# Brians_test_board_10.net
KiCad netlist of a schematic drawn in EAGLE
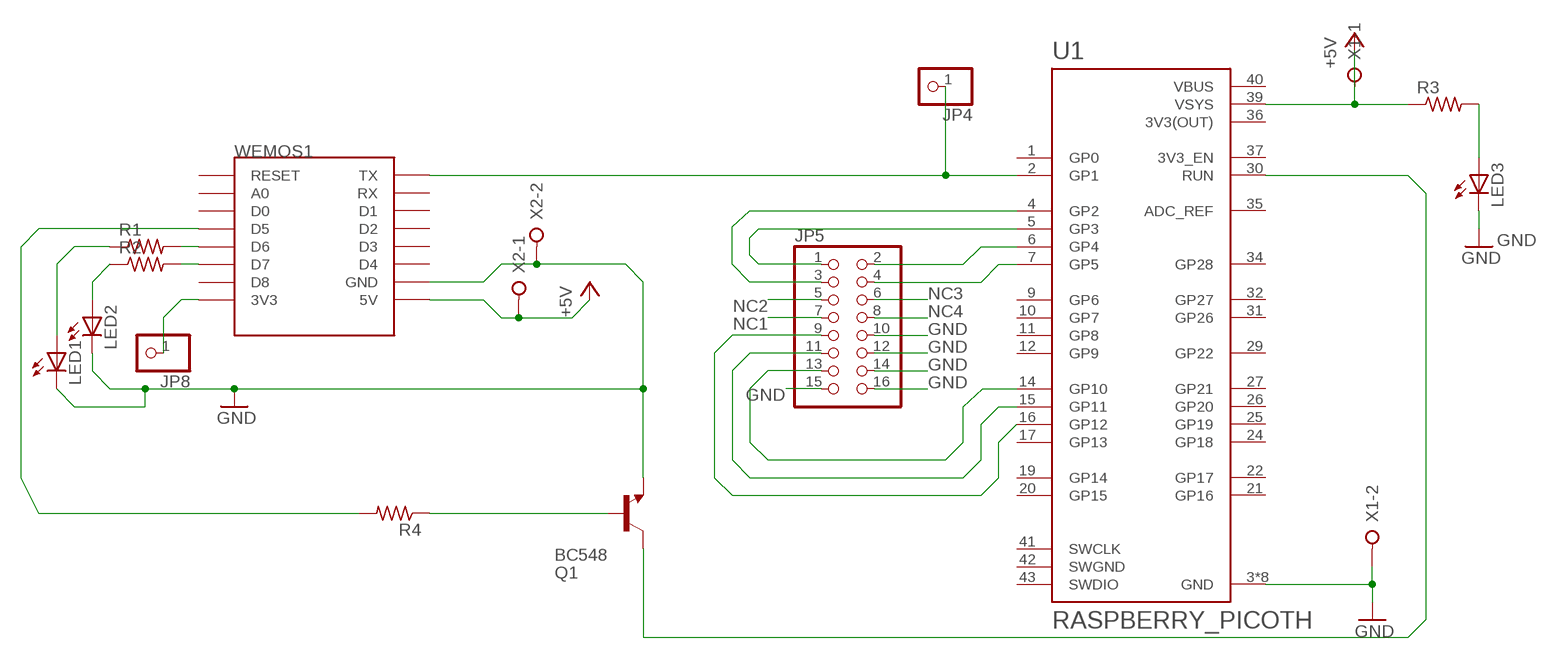
[diagram p0: schematic, sheet 1]

(export (version "E")
  (design (tool "Eeschema 10.0.6"))
  (components
    (comp (ref "JP4")
      (value "PINHD-1X1")
      (footprint "eagle-import:1X01")
      (libsource (lib "eagle-import") (part "PINHD-1X1"))
    )
    (comp (ref "JP5")
      (value "PINHD-2X8")
      (footprint "eagle-import:2X08")
      (libsource (lib "eagle-import") (part "PINHD-2X8"))
    )
    (comp (ref "JP8")
      (value "PINHD-1X1")
      (footprint "eagle-import:1X01")
      (libsource (lib "eagle-import") (part "PINHD-1X1"))
    )
    (comp (ref "LED1")
      (value "LED3MM")
      (footprint "eagle-import:LED3MM")
      (libsource (lib "eagle-import") (part "LED3MM"))
    )
    (comp (ref "LED2")
      (value "LED3MM")
      (footprint "eagle-import:LED3MM")
      (libsource (lib "eagle-import") (part "LED3MM"))
    )
    (comp (ref "LED3")
      (value "LED3MM")
      (footprint "eagle-import:LED3MM")
      (libsource (lib "eagle-import") (part "LED3MM"))
    )
    (comp (ref "Q1")
      (value "BC548")
      (footprint "eagle-import:TO92-EBC")
      (libsource (lib "eagle-import") (part "BC548"))
    )
    (comp (ref "R1")
      (value "R-US_0204/2V")
      (footprint "eagle-import:0204V")
      (libsource (lib "eagle-import") (part "R-US_0204/2V"))
    )
    (comp (ref "R2")
      (value "R-US_0204/2V")
      (footprint "eagle-import:0204V")
      (libsource (lib "eagle-import") (part "R-US_0204/2V"))
    )
    (comp (ref "R3")
      (value "R-US_0204/5")
      (footprint "eagle-import:0204_5")
      (libsource (lib "eagle-import") (part "R-US_0204/5"))
    )
    (comp (ref "R4")
      (value "R-US_0204/2V")
      (footprint "eagle-import:0204V")
      (libsource (lib "eagle-import") (part "R-US_0204/2V"))
    )
    (comp (ref "U1")
      (value "RASPBERRY_PICOTH")
      (footprint "eagle-import:PICO-PKG-TH")
      (libsource (lib "eagle-import") (part "RASPBERRY_PICOTH"))
    )
    (comp (ref "WEMOS1")
      (value "WEMOS-D1-MINI")
      (footprint "eagle-import:WEMOS-D1-MINI")
      (libsource (lib "eagle-import") (part "WEMOS-D1-MINI"))
    )
    (comp (ref "X1")
      (value "W237-02P")
      (footprint "eagle-import:W237-132")
      (libsource (lib "eagle-import") (part "W237-02P"))
    )
    (comp (ref "X2")
      (value "W237-02P")
      (footprint "eagle-import:W237-132")
      (libsource (lib "eagle-import") (part "W237-02P"))
    )
  )
  (nets
    (net (code "1") (name "+5V") (class "Default")
      (node (ref "R3") (pin "1") (pinfunction "1_1") (pintype "passive"))
      (node (ref "U1") (pin "39") (pinfunction "VSYS_39") (pintype "power_in"))
      (node (ref "WEMOS1") (pin "5V") (pinfunction "5V_5V") (pintype "bidirectional"))
      (node (ref "X1") (pin "1") (pinfunction "KL_1") (pintype "passive"))
      (node (ref "X2") (pin "1") (pinfunction "KL_1") (pintype "passive"))
    )
    (net (code "2") (name "/3V3(OUT)") (class "Default")
      (node (ref "U1") (pin "36") (pinfunction "3V3(OUT)_36") (pintype "power_in"))
    )
    (net (code "3") (name "/NC1") (class "Default")
      (node (ref "JP5") (pin "7") (pinfunction "7_7") (pintype "passive"))
    )
    (net (code "4") (name "/NC2") (class "Default")
      (node (ref "JP5") (pin "5") (pinfunction "5_5") (pintype "passive"))
    )
    (net (code "5") (name "/NC3") (class "Default")
      (node (ref "JP5") (pin "6") (pinfunction "6_6") (pintype "passive"))
    )
    (net (code "6") (name "/NC4") (class "Default")
      (node (ref "JP5") (pin "8") (pinfunction "8_8") (pintype "passive"))
    )
    (net (code "7") (name "/SWGND") (class "Default")
      (node (ref "U1") (pin "42") (pinfunction "SWGND_42") (pintype "power_in"))
    )
    (net (code "8") (name "/VBUS") (class "Default")
      (node (ref "U1") (pin "40") (pinfunction "VBUS_40") (pintype "power_in"))
    )
    (net (code "9") (name "GND") (class "Default")
      (node (ref "JP5") (pin "10") (pinfunction "10_10") (pintype "passive"))
      (node (ref "JP5") (pin "12") (pinfunction "12_12") (pintype "passive"))
      (node (ref "JP5") (pin "14") (pinfunction "14_14") (pintype "passive"))
      (node (ref "JP5") (pin "15") (pinfunction "15_15") (pintype "passive"))
      (node (ref "JP5") (pin "16") (pinfunction "16_16") (pintype "passive"))
      (node (ref "LED1") (pin "K") (pinfunction "C_K") (pintype "passive"))
      (node (ref "LED2") (pin "K") (pinfunction "C_K") (pintype "passive"))
      (node (ref "LED3") (pin "K") (pinfunction "C_K") (pintype "passive"))
      (node (ref "Q1") (pin "E") (pinfunction "E_E") (pintype "passive"))
      (node (ref "U1") (pin "13") (pinfunction "GND_13") (pintype "power_in"))
      (node (ref "U1") (pin "18") (pinfunction "GND_18") (pintype "power_in"))
      (node (ref "U1") (pin "23") (pinfunction "GND_23") (pintype "power_in"))
      (node (ref "U1") (pin "28") (pinfunction "GND_28") (pintype "power_in"))
      (node (ref "U1") (pin "3") (pinfunction "GND_3") (pintype "power_in"))
      (node (ref "U1") (pin "33") (pinfunction "GND_33") (pintype "power_in"))
      (node (ref "U1") (pin "38") (pinfunction "GND_38") (pintype "power_in"))
      (node (ref "U1") (pin "8") (pinfunction "GND_8") (pintype "power_in"))
      (node (ref "WEMOS1") (pin "GND") (pinfunction "GND_GND") (pintype "bidirectional"))
      (node (ref "X1") (pin "2") (pinfunction "KL_2") (pintype "passive"))
      (node (ref "X2") (pin "2") (pinfunction "KL_2") (pintype "passive"))
    )
    (net (code "10") (name "Net-(JP8-Pad1)") (class "Default")
      (node (ref "JP8") (pin "1") (pinfunction "1_1") (pintype "passive"))
      (node (ref "WEMOS1") (pin "3V3") (pinfunction "3V3_3V3") (pintype "bidirectional"))
    )
    (net (code "11") (name "Net-(LED1-PadA)") (class "Default")
      (node (ref "LED1") (pin "A") (pinfunction "A_A") (pintype "passive"))
      (node (ref "R1") (pin "1") (pinfunction "1_1") (pintype "passive"))
    )
    (net (code "12") (name "Net-(LED2-PadA)") (class "Default")
      (node (ref "LED2") (pin "A") (pinfunction "A_A") (pintype "passive"))
      (node (ref "R2") (pin "1") (pinfunction "1_1") (pintype "passive"))
    )
    (net (code "13") (name "Net-(LED3-PadA)") (class "Default")
      (node (ref "LED3") (pin "A") (pinfunction "A_A") (pintype "passive"))
      (node (ref "R3") (pin "2") (pinfunction "2_2") (pintype "passive"))
    )
    (net (code "14") (name "Net-(Q1-PadB)") (class "Default")
      (node (ref "Q1") (pin "B") (pinfunction "B_B") (pintype "passive"))
      (node (ref "R4") (pin "1") (pinfunction "1_1") (pintype "passive"))
    )
    (net (code "15") (name "Net-(R1-Pad2)") (class "Default")
      (node (ref "R1") (pin "2") (pinfunction "2_2") (pintype "passive"))
      (node (ref "WEMOS1") (pin "D6") (pinfunction "D6_D6") (pintype "bidirectional"))
    )
    (net (code "16") (name "Net-(R2-Pad2)") (class "Default")
      (node (ref "R2") (pin "2") (pinfunction "2_2") (pintype "passive"))
      (node (ref "WEMOS1") (pin "D7") (pinfunction "D7_D7") (pintype "bidirectional"))
    )
    (net (code "17") (name "Net-(R4-Pad2)") (class "Default")
      (node (ref "R4") (pin "2") (pinfunction "2_2") (pintype "passive"))
      (node (ref "WEMOS1") (pin "D5") (pinfunction "D5_D5") (pintype "bidirectional"))
    )
    (net (code "18") (name "Net-(U1-GP1)") (class "Default")
      (node (ref "JP4") (pin "1") (pinfunction "1_1") (pintype "passive"))
      (node (ref "U1") (pin "2") (pinfunction "GP1_2") (pintype "bidirectional"))
      (node (ref "WEMOS1") (pin "TX") (pinfunction "TX_TX") (pintype "bidirectional"))
    )
    (net (code "19") (name "Net-(U1-GP2)") (class "Default")
      (node (ref "JP5") (pin "3") (pinfunction "3_3") (pintype "passive"))
      (node (ref "U1") (pin "4") (pinfunction "GP2_4") (pintype "bidirectional"))
    )
    (net (code "20") (name "Net-(U1-GP3)") (class "Default")
      (node (ref "JP5") (pin "1") (pinfunction "1_1") (pintype "passive"))
      (node (ref "U1") (pin "5") (pinfunction "GP3_5") (pintype "bidirectional"))
    )
    (net (code "21") (name "Net-(U1-GP4)") (class "Default")
      (node (ref "JP5") (pin "2") (pinfunction "2_2") (pintype "passive"))
      (node (ref "U1") (pin "6") (pinfunction "GP4_6") (pintype "bidirectional"))
    )
    (net (code "22") (name "Net-(U1-GP5)") (class "Default")
      (node (ref "JP5") (pin "4") (pinfunction "4_4") (pintype "passive"))
      (node (ref "U1") (pin "7") (pinfunction "GP5_7") (pintype "bidirectional"))
    )
    (net (code "23") (name "Net-(U1-GP10)") (class "Default")
      (node (ref "JP5") (pin "13") (pinfunction "13_13") (pintype "passive"))
      (node (ref "U1") (pin "14") (pinfunction "GP10_14") (pintype "bidirectional"))
    )
    (net (code "24") (name "Net-(U1-GP11)") (class "Default")
      (node (ref "JP5") (pin "11") (pinfunction "11_11") (pintype "passive"))
      (node (ref "U1") (pin "15") (pinfunction "GP11_15") (pintype "bidirectional"))
    )
    (net (code "25") (name "Net-(U1-GP12)") (class "Default")
      (node (ref "JP5") (pin "9") (pinfunction "9_9") (pintype "passive"))
      (node (ref "U1") (pin "16") (pinfunction "GP12_16") (pintype "bidirectional"))
    )
    (net (code "26") (name "Net-(U1-RUN)") (class "Default")
      (node (ref "Q1") (pin "C") (pinfunction "C_C") (pintype "passive"))
      (node (ref "U1") (pin "30") (pinfunction "RUN_30") (pintype "input"))
    )
    (net (code "27") (name "unconnected-(U1-3V3_EN-Pad37)") (class "Default")
      (node (ref "U1") (pin "37") (pinfunction "3V3_EN_37") (pintype "input"))
    )
    (net (code "28") (name "unconnected-(U1-ADC_REF-Pad35)") (class "Default")
      (node (ref "U1") (pin "35") (pinfunction "ADC_REF_35") (pintype "input"))
    )
    (net (code "29") (name "unconnected-(U1-GP0-Pad1)") (class "Default")
      (node (ref "U1") (pin "1") (pinfunction "GP0_1") (pintype "bidirectional"))
    )
    (net (code "30") (name "unconnected-(U1-GP6-Pad9)") (class "Default")
      (node (ref "U1") (pin "9") (pinfunction "GP6_9") (pintype "bidirectional"))
    )
    (net (code "31") (name "unconnected-(U1-GP7-Pad10)") (class "Default")
      (node (ref "U1") (pin "10") (pinfunction "GP7_10") (pintype "bidirectional"))
    )
    (net (code "32") (name "unconnected-(U1-GP8-Pad11)") (class "Default")
      (node (ref "U1") (pin "11") (pinfunction "GP8_11") (pintype "bidirectional"))
    )
    (net (code "33") (name "unconnected-(U1-GP9-Pad12)") (class "Default")
      (node (ref "U1") (pin "12") (pinfunction "GP9_12") (pintype "bidirectional"))
    )
    (net (code "34") (name "unconnected-(U1-GP13-Pad17)") (class "Default")
      (node (ref "U1") (pin "17") (pinfunction "GP13_17") (pintype "bidirectional"))
    )
    (net (code "35") (name "unconnected-(U1-GP14-Pad19)") (class "Default")
      (node (ref "U1") (pin "19") (pinfunction "GP14_19") (pintype "bidirectional"))
    )
    (net (code "36") (name "unconnected-(U1-GP15-Pad20)") (class "Default")
      (node (ref "U1") (pin "20") (pinfunction "GP15_20") (pintype "bidirectional"))
    )
    (net (code "37") (name "unconnected-(U1-GP16-Pad21)") (class "Default")
      (node (ref "U1") (pin "21") (pinfunction "GP16_21") (pintype "bidirectional"))
    )
    (net (code "38") (name "unconnected-(U1-GP17-Pad22)") (class "Default")
      (node (ref "U1") (pin "22") (pinfunction "GP17_22") (pintype "bidirectional"))
    )
    (net (code "39") (name "unconnected-(U1-GP18-Pad24)") (class "Default")
      (node (ref "U1") (pin "24") (pinfunction "GP18_24") (pintype "bidirectional"))
    )
    (net (code "40") (name "unconnected-(U1-GP19-Pad25)") (class "Default")
      (node (ref "U1") (pin "25") (pinfunction "GP19_25") (pintype "bidirectional"))
    )
    (net (code "41") (name "unconnected-(U1-GP20-Pad26)") (class "Default")
      (node (ref "U1") (pin "26") (pinfunction "GP20_26") (pintype "bidirectional"))
    )
    (net (code "42") (name "unconnected-(U1-GP21-Pad27)") (class "Default")
      (node (ref "U1") (pin "27") (pinfunction "GP21_27") (pintype "bidirectional"))
    )
    (net (code "43") (name "unconnected-(U1-GP22-Pad29)") (class "Default")
      (node (ref "U1") (pin "29") (pinfunction "GP22_29") (pintype "bidirectional"))
    )
    (net (code "44") (name "unconnected-(U1-GP26-Pad31)") (class "Default")
      (node (ref "U1") (pin "31") (pinfunction "GP26_31") (pintype "bidirectional"))
    )
    (net (code "45") (name "unconnected-(U1-GP27-Pad32)") (class "Default")
      (node (ref "U1") (pin "32") (pinfunction "GP27_32") (pintype "bidirectional"))
    )
    (net (code "46") (name "unconnected-(U1-GP28-Pad34)") (class "Default")
      (node (ref "U1") (pin "34") (pinfunction "GP28_34") (pintype "bidirectional"))
    )
    (net (code "47") (name "unconnected-(U1-SWCLK-Pad41)") (class "Default")
      (node (ref "U1") (pin "41") (pinfunction "SWCLK_41") (pintype "input"))
    )
    (net (code "48") (name "unconnected-(U1-SWDIO-Pad43)") (class "Default")
      (node (ref "U1") (pin "43") (pinfunction "SWDIO_43") (pintype "bidirectional"))
    )
    (net (code "49") (name "unconnected-(WEMOS1-PadA0)") (class "Default")
      (node (ref "WEMOS1") (pin "A0") (pinfunction "A0_A0") (pintype "bidirectional"))
    )
    (net (code "50") (name "unconnected-(WEMOS1-PadD0)") (class "Default")
      (node (ref "WEMOS1") (pin "D0") (pinfunction "D0_D0") (pintype "bidirectional"))
    )
    (net (code "51") (name "unconnected-(WEMOS1-PadD1)") (class "Default")
      (node (ref "WEMOS1") (pin "D1") (pinfunction "D1_D1") (pintype "bidirectional"))
    )
    (net (code "52") (name "unconnected-(WEMOS1-PadD2)") (class "Default")
      (node (ref "WEMOS1") (pin "D2") (pinfunction "D2_D2") (pintype "bidirectional"))
    )
    (net (code "53") (name "unconnected-(WEMOS1-PadD3)") (class "Default")
      (node (ref "WEMOS1") (pin "D3") (pinfunction "D3_D3") (pintype "bidirectional"))
    )
    (net (code "54") (name "unconnected-(WEMOS1-PadD4)") (class "Default")
      (node (ref "WEMOS1") (pin "D4") (pinfunction "D4_D4") (pintype "bidirectional"))
    )
    (net (code "55") (name "unconnected-(WEMOS1-PadD8)") (class "Default")
      (node (ref "WEMOS1") (pin "D8") (pinfunction "D8_D8") (pintype "bidirectional"))
    )
    (net (code "56") (name "unconnected-(WEMOS1-PadRESET)") (class "Default")
      (node (ref "WEMOS1") (pin "RESET") (pinfunction "RESET_RESET") (pintype "bidirectional"))
    )
    (net (code "57") (name "unconnected-(WEMOS1-PadRX)") (class "Default")
      (node (ref "WEMOS1") (pin "RX") (pinfunction "RX_RX") (pintype "bidirectional"))
    )
  )
)
